# i12_TEMPERATURESENSOR-v03_3_4_OHW.net
KiCad netlist of a schematic drawn in EAGLE
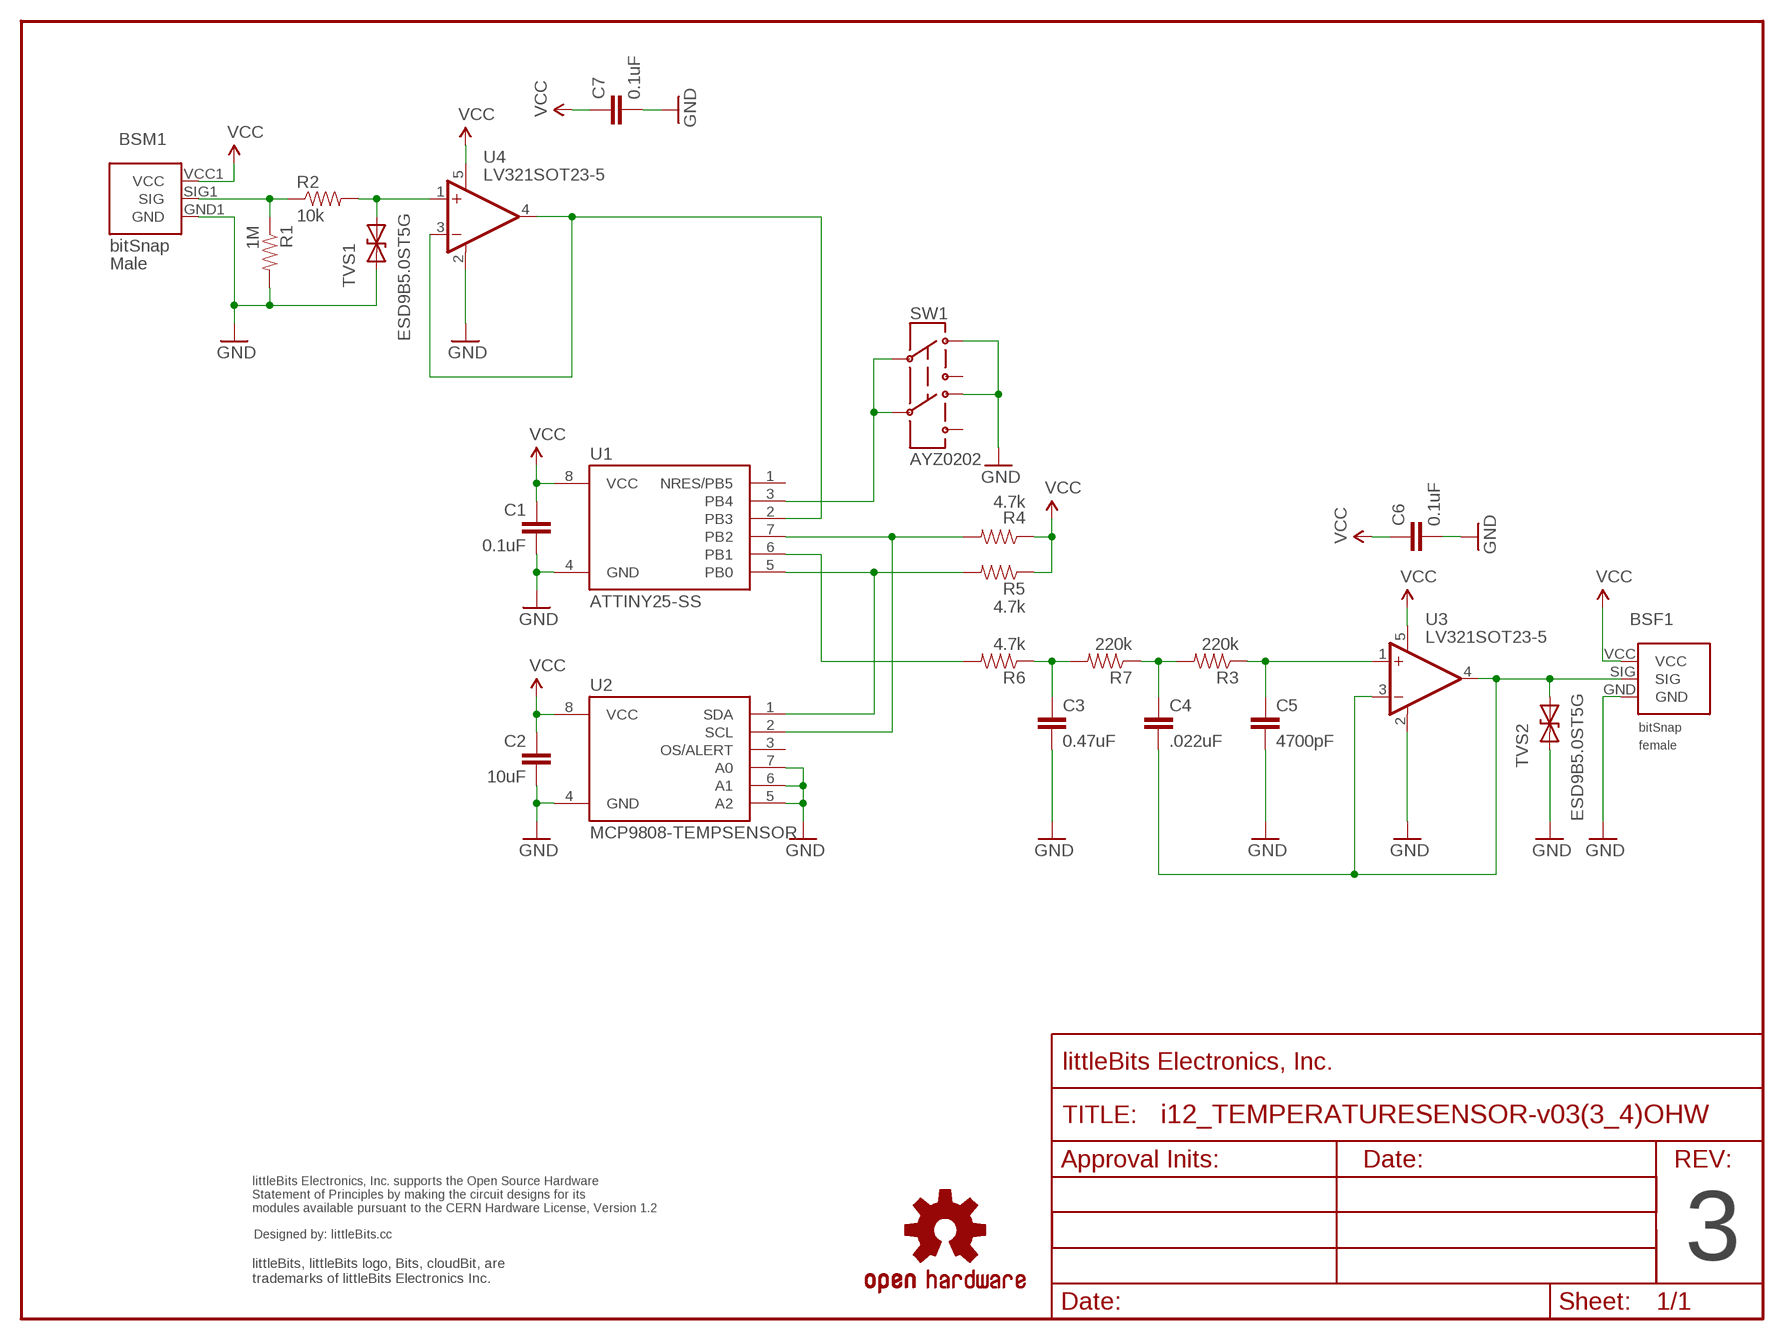
[diagram p0: schematic, sheet 1]

(export (version "E")
  (design (tool "Eeschema 10.0.6"))
  (components
    (comp (ref "BSF1")
      (value "BITSNAP_V03_FEMALE")
      (footprint "eagle-import:BITSNAP_V03_FEMALE")
      (libsource (lib "eagle-import") (part "BITSNAP_V03_FEMALE"))
    )
    (comp (ref "BSM1")
      (value "BITSNAP_V03_MALE")
      (footprint "eagle-import:BITSNAP_V03_MALE")
      (libsource (lib "eagle-import") (part "BITSNAP_V03_MALE"))
    )
    (comp (ref "C1")
      (value "0.1uF")
      (footprint "eagle-import:CAP-0603")
      (libsource (lib "eagle-import") (part "CAPCAP-0603"))
    )
    (comp (ref "C2")
      (value "10uF")
      (footprint "eagle-import:CAP-0603")
      (libsource (lib "eagle-import") (part "CAPCAP-0603"))
    )
    (comp (ref "C3")
      (value "0.47uF")
      (footprint "eagle-import:CAP-0603")
      (libsource (lib "eagle-import") (part "CAPCAP-0603"))
    )
    (comp (ref "C4")
      (value ".022uF")
      (footprint "eagle-import:CAP-0603")
      (libsource (lib "eagle-import") (part "CAPCAP-0603"))
    )
    (comp (ref "C5")
      (value "4700pF")
      (footprint "eagle-import:CAP-0603")
      (libsource (lib "eagle-import") (part "CAPCAP-0603"))
    )
    (comp (ref "C6")
      (value "0.1uF")
      (footprint "eagle-import:CAP-0603")
      (libsource (lib "eagle-import") (part "CAPCAP-0603"))
    )
    (comp (ref "C7")
      (value "0.1uF")
      (footprint "eagle-import:CAP-0603")
      (libsource (lib "eagle-import") (part "CAPCAP-0603"))
    )
    (comp (ref "R1")
      (value "1M")
      (footprint "eagle-import:RES-0603")
      (libsource (lib "eagle-import") (part "RESISTOR0603"))
    )
    (comp (ref "R2")
      (value "10k")
      (footprint "eagle-import:RES-0603")
      (libsource (lib "eagle-import") (part "RESISTOR0603"))
    )
    (comp (ref "R3")
      (value "220k")
      (footprint "eagle-import:RES-0603")
      (libsource (lib "eagle-import") (part "RESISTOR0603"))
    )
    (comp (ref "R4")
      (value "4.7k")
      (footprint "eagle-import:RES-0603")
      (libsource (lib "eagle-import") (part "RESISTOR0603"))
    )
    (comp (ref "R5")
      (value "4.7k")
      (footprint "eagle-import:RES-0603")
      (libsource (lib "eagle-import") (part "RESISTOR0603"))
    )
    (comp (ref "R6")
      (value "4.7k")
      (footprint "eagle-import:RES-0603")
      (libsource (lib "eagle-import") (part "RESISTOR0603"))
    )
    (comp (ref "R7")
      (value "220k")
      (footprint "eagle-import:RES-0603")
      (libsource (lib "eagle-import") (part "RESISTOR0603"))
    )
    (comp (ref "SW1")
      (value "AYZ0202")
      (footprint "eagle-import:AYZ0202")
      (libsource (lib "eagle-import") (part "AYZ0202"))
    )
    (comp (ref "TVS1")
      (value "ESD9B5.0ST5G")
      (footprint "eagle-import:SOD-923")
      (libsource (lib "eagle-import") (part "DIODE-TVSSOD-923"))
    )
    (comp (ref "TVS2")
      (value "ESD9B5.0ST5G")
      (footprint "eagle-import:SOD-923")
      (libsource (lib "eagle-import") (part "DIODE-TVSSOD-923"))
    )
    (comp (ref "U$4")
      (value "OSHWCREDIT")
      (footprint "eagle-import:OSHWCREDIT")
      (libsource (lib "eagle-import") (part "OSHWCREDIT"))
    )
    (comp (ref "U$5")
      (value "OSHW-LOGOL")
      (footprint "eagle-import:OSHW-LOGO-L")
      (libsource (lib "eagle-import") (part "OSHW-LOGOL"))
    )
    (comp (ref "U$33")
      (value "FRAME-LETTER-OHWOHW")
      (footprint "eagle-import:FABDWG01-OHW")
      (libsource (lib "eagle-import") (part "FRAME-LETTER-OHWOHW"))
    )
    (comp (ref "U1")
      (value "ATTINY25-SS")
      (footprint "eagle-import:SOIC08_JEDEC_150MIL")
      (libsource (lib "eagle-import") (part "ATTINY25SS-"))
    )
    (comp (ref "U2")
      (value "MCP9808-TEMPSENSOR")
      (footprint "eagle-import:MICRO8-ON")
      (libsource (lib "eagle-import") (part "MCP9808-TEMPSENSOR"))
    )
    (comp (ref "U3")
      (value "LV321SOT23-5")
      (footprint "eagle-import:SOT23-5")
      (libsource (lib "eagle-import") (part "LV321SOT23-5"))
    )
    (comp (ref "U4")
      (value "LV321SOT23-5")
      (footprint "eagle-import:SOT23-5")
      (libsource (lib "eagle-import") (part "LV321SOT23-5"))
    )
  )
  (nets
    (net (code "1") (name "GND") (class "Default")
      (node (ref "BSF1") (pin "GND") (pinfunction "GND_GND") (pintype "bidirectional"))
      (node (ref "BSM1") (pin "GND1") (pinfunction "GND_GND1") (pintype "bidirectional"))
      (node (ref "C1") (pin "2") (pinfunction "2_2") (pintype "passive"))
      (node (ref "C2") (pin "2") (pinfunction "2_2") (pintype "passive"))
      (node (ref "C3") (pin "2") (pinfunction "2_2") (pintype "passive"))
      (node (ref "C5") (pin "2") (pinfunction "2_2") (pintype "passive"))
      (node (ref "C6") (pin "2") (pinfunction "2_2") (pintype "passive"))
      (node (ref "C7") (pin "2") (pinfunction "2_2") (pintype "passive"))
      (node (ref "R1") (pin "2") (pinfunction "2_2") (pintype "passive"))
      (node (ref "SW1") (pin "1") (pinfunction "1_1") (pintype "bidirectional"))
      (node (ref "SW1") (pin "4") (pinfunction "4_4") (pintype "bidirectional"))
      (node (ref "TVS1") (pin "1") (pinfunction "A_1") (pintype "passive"))
      (node (ref "TVS2") (pin "1") (pinfunction "A_1") (pintype "passive"))
      (node (ref "U1") (pin "4") (pinfunction "GND_4") (pintype "power_in"))
      (node (ref "U2") (pin "4") (pinfunction "GND_4") (pintype "power_in"))
      (node (ref "U2") (pin "5") (pinfunction "A2_5") (pintype "input"))
      (node (ref "U2") (pin "6") (pinfunction "A1_6") (pintype "input"))
      (node (ref "U2") (pin "7") (pinfunction "A0_7") (pintype "input"))
      (node (ref "U3") (pin "2") (pinfunction "V-_2") (pintype "power_in"))
      (node (ref "U4") (pin "2") (pinfunction "V-_2") (pintype "power_in"))
    )
    (net (code "2") (name "Net-(BSM1-SIG)") (class "Default")
      (node (ref "BSM1") (pin "SIG1") (pinfunction "SIG_SIG1") (pintype "bidirectional"))
      (node (ref "R1") (pin "1") (pinfunction "1_1") (pintype "passive"))
      (node (ref "R2") (pin "1") (pinfunction "1_1") (pintype "passive"))
    )
    (net (code "3") (name "Net-(C3-Pad1)") (class "Default")
      (node (ref "C3") (pin "1") (pinfunction "1_1") (pintype "passive"))
      (node (ref "R6") (pin "1") (pinfunction "1_1") (pintype "passive"))
      (node (ref "R7") (pin "2") (pinfunction "2_2") (pintype "passive"))
    )
    (net (code "4") (name "Net-(C4-Pad1)") (class "Default")
      (node (ref "C4") (pin "1") (pinfunction "1_1") (pintype "passive"))
      (node (ref "R3") (pin "2") (pinfunction "2_2") (pintype "passive"))
      (node (ref "R7") (pin "1") (pinfunction "1_1") (pintype "passive"))
    )
    (net (code "5") (name "Net-(TVS1-C)") (class "Default")
      (node (ref "R2") (pin "2") (pinfunction "2_2") (pintype "passive"))
      (node (ref "TVS1") (pin "2") (pinfunction "C_2") (pintype "passive"))
      (node (ref "U4") (pin "1") (pinfunction "+IN_1") (pintype "input"))
    )
    (net (code "6") (name "Net-(TVS2-C)") (class "Default")
      (node (ref "BSF1") (pin "SIG") (pinfunction "SIG_SIG") (pintype "bidirectional"))
      (node (ref "C4") (pin "2") (pinfunction "2_2") (pintype "passive"))
      (node (ref "TVS2") (pin "2") (pinfunction "C_2") (pintype "passive"))
      (node (ref "U3") (pin "3") (pinfunction "-IN_3") (pintype "input"))
      (node (ref "U3") (pin "4") (pinfunction "OUT_4") (pintype "output"))
    )
    (net (code "7") (name "Net-(U1-PB0)") (class "Default")
      (node (ref "R5") (pin "2") (pinfunction "2_2") (pintype "passive"))
      (node (ref "U1") (pin "5") (pinfunction "PB0_5") (pintype "bidirectional"))
      (node (ref "U2") (pin "1") (pinfunction "SDA_1") (pintype "bidirectional"))
    )
    (net (code "8") (name "Net-(U1-PB1)") (class "Default")
      (node (ref "R6") (pin "2") (pinfunction "2_2") (pintype "passive"))
      (node (ref "U1") (pin "6") (pinfunction "PB1_6") (pintype "bidirectional"))
    )
    (net (code "9") (name "Net-(U1-PB2)") (class "Default")
      (node (ref "R4") (pin "2") (pinfunction "2_2") (pintype "passive"))
      (node (ref "U1") (pin "7") (pinfunction "PB2_7") (pintype "bidirectional"))
      (node (ref "U2") (pin "2") (pinfunction "SCL_2") (pintype "input"))
    )
    (net (code "10") (name "Net-(U1-PB3)") (class "Default")
      (node (ref "U1") (pin "2") (pinfunction "PB3_2") (pintype "bidirectional"))
      (node (ref "U4") (pin "3") (pinfunction "-IN_3") (pintype "input"))
      (node (ref "U4") (pin "4") (pinfunction "OUT_4") (pintype "output"))
    )
    (net (code "11") (name "Net-(U1-PB4)") (class "Default")
      (node (ref "SW1") (pin "2") (pinfunction "2_2") (pintype "bidirectional"))
      (node (ref "SW1") (pin "5") (pinfunction "5_5") (pintype "bidirectional"))
      (node (ref "U1") (pin "3") (pinfunction "PB4_3") (pintype "bidirectional"))
    )
    (net (code "12") (name "Net-(U3-+IN)") (class "Default")
      (node (ref "C5") (pin "1") (pinfunction "1_1") (pintype "passive"))
      (node (ref "R3") (pin "1") (pinfunction "1_1") (pintype "passive"))
      (node (ref "U3") (pin "1") (pinfunction "+IN_1") (pintype "input"))
    )
    (net (code "13") (name "VCC") (class "Default")
      (node (ref "BSF1") (pin "VCC") (pinfunction "VCC_VCC") (pintype "bidirectional"))
      (node (ref "BSM1") (pin "VCC1") (pinfunction "VCC_VCC1") (pintype "bidirectional"))
      (node (ref "C1") (pin "1") (pinfunction "1_1") (pintype "passive"))
      (node (ref "C2") (pin "1") (pinfunction "1_1") (pintype "passive"))
      (node (ref "C6") (pin "1") (pinfunction "1_1") (pintype "passive"))
      (node (ref "C7") (pin "1") (pinfunction "1_1") (pintype "passive"))
      (node (ref "R4") (pin "1") (pinfunction "1_1") (pintype "passive"))
      (node (ref "R5") (pin "1") (pinfunction "1_1") (pintype "passive"))
      (node (ref "U1") (pin "8") (pinfunction "VCC_8") (pintype "power_in"))
      (node (ref "U2") (pin "8") (pinfunction "VCC_8") (pintype "power_in"))
      (node (ref "U3") (pin "5") (pinfunction "V+_5") (pintype "power_in"))
      (node (ref "U4") (pin "5") (pinfunction "V+_5") (pintype "power_in"))
    )
    (net (code "14") (name "unconnected-(SW1-Pad3)") (class "Default")
      (node (ref "SW1") (pin "3") (pinfunction "3_3") (pintype "bidirectional"))
    )
    (net (code "15") (name "unconnected-(SW1-Pad6)") (class "Default")
      (node (ref "SW1") (pin "6") (pinfunction "6_6") (pintype "bidirectional"))
    )
    (net (code "16") (name "unconnected-(U1-NRES{slash}PB5-Pad1)") (class "Default")
      (node (ref "U1") (pin "1") (pinfunction "NRES/PB5_1") (pintype "bidirectional"))
    )
    (net (code "17") (name "unconnected-(U2-OS{slash}ALERT-Pad3)") (class "Default")
      (node (ref "U2") (pin "3") (pinfunction "OS/ALERT_3") (pintype "output"))
    )
  )
)
